# PWM.net
KiCad netlist of a schematic drawn in EAGLE
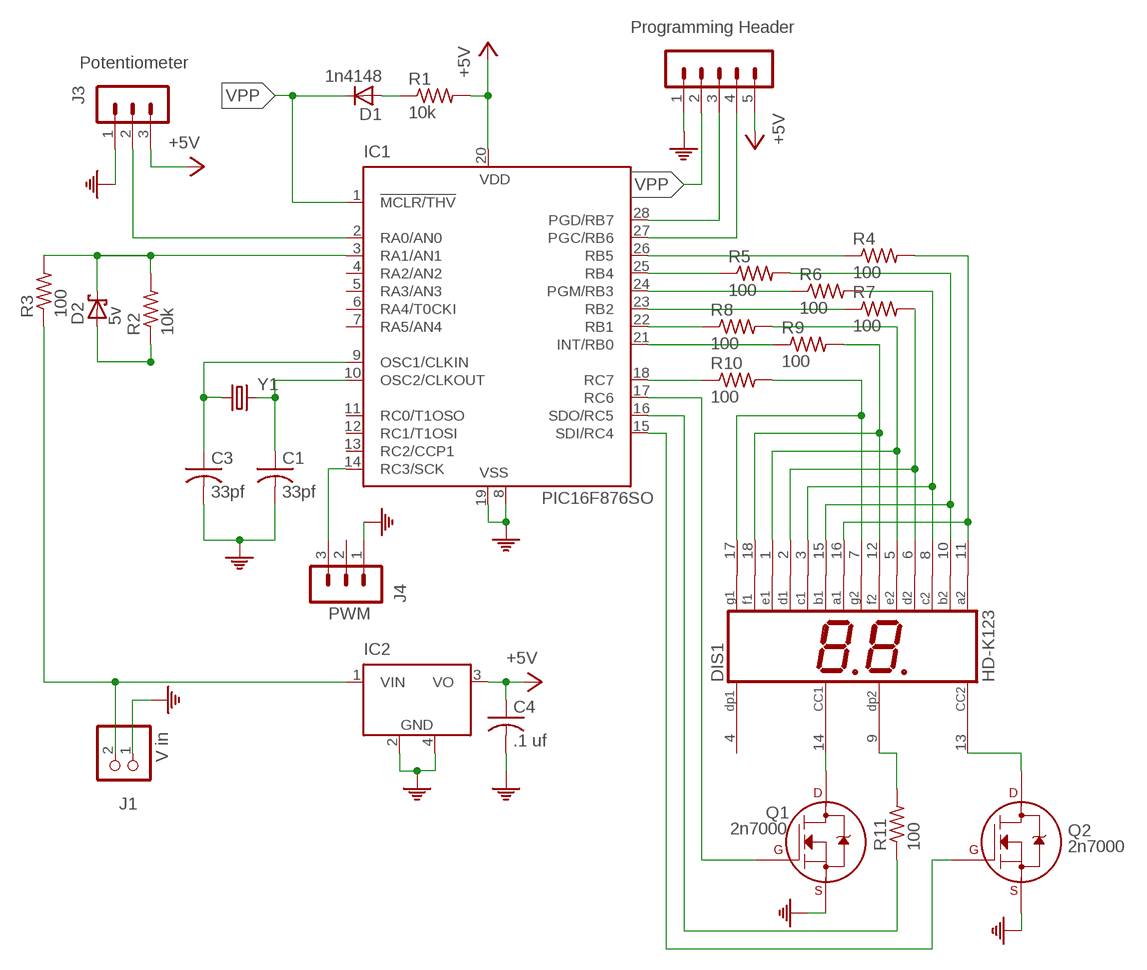
[diagram p0: schematic, sheet 1]

(export (version "E")
  (design (tool "Eeschema 10.0.6"))
  (components
    (comp (ref "C1")
      (value "33pf")
      (footprint "eagle-import:C0402K")
      (libsource (lib "eagle-import") (part "C-USC0402K"))
    )
    (comp (ref "C3")
      (value "33pf")
      (footprint "eagle-import:C0402K")
      (libsource (lib "eagle-import") (part "C-USC0402K"))
    )
    (comp (ref "C4")
      (value ".1 uf")
      (footprint "eagle-import:C0402K")
      (libsource (lib "eagle-import") (part "C-USC0402K"))
    )
    (comp (ref "D1")
      (value "1n4148")
      (footprint "eagle-import:SOD123")
      (libsource (lib "eagle-import") (part "D-SOD123"))
    )
    (comp (ref "D2")
      (value "5v")
      (footprint "eagle-import:SOD323_ST")
      (libsource (lib "eagle-import") (part "BAT60J"))
    )
    (comp (ref "DIS1")
      (value "HD-K123")
      (footprint "eagle-import:HDSP-R")
      (libsource (lib "eagle-import") (part "HD-K123"))
    )
    (comp (ref "IC1")
      (value "PIC16F876SO")
      (footprint "eagle-import:SO28W")
      (fields (field (name "MF") "MICROCHIP") (field (name "MPN") "PIC16F876-20/SO"))
      (libsource (lib "eagle-import") (part "PIC16876SOF"))
    )
    (comp (ref "IC2")
      (value "LM2936MP-5.0")
      (footprint "eagle-import:SOT223")
      (fields (field (name "MF") "NATIONAL SEMICONDUCTOR") (field (name "MPN") "LM2936MP-5.0/NOPB"))
      (libsource (lib "eagle-import") (part "LM2936MP?-5.0"))
    )
    (comp (ref "J1")
      (value "V in")
      (footprint "eagle-import:1X02")
      (libsource (lib "eagle-import") (part "PINHD-1X2"))
    )
    (comp (ref "J2")
      (value "Programming Header")
      (footprint "eagle-import:MA05-1")
      (libsource (lib "eagle-import") (part "MA05-1"))
    )
    (comp (ref "J3")
      (value "Potentiometer")
      (footprint "eagle-import:MA03-1")
      (libsource (lib "eagle-import") (part "MA03-1"))
    )
    (comp (ref "J4")
      (value "PWM")
      (footprint "eagle-import:MA03-1")
      (libsource (lib "eagle-import") (part "MA03-1"))
    )
    (comp (ref "Q1")
      (value "2n7000")
      (footprint "eagle-import:TO-92")
      (libsource (lib "eagle-import") (part "2N700_TO920"))
    )
    (comp (ref "Q2")
      (value "2n7000")
      (footprint "eagle-import:TO-92")
      (libsource (lib "eagle-import") (part "2N700_TO920"))
    )
    (comp (ref "R1")
      (value "10k")
      (footprint "eagle-import:R2012")
      (libsource (lib "eagle-import") (part "R-US_R2012"))
    )
    (comp (ref "R2")
      (value "10k")
      (footprint "eagle-import:R2012")
      (libsource (lib "eagle-import") (part "R-US_R2012"))
    )
    (comp (ref "R3")
      (value "100")
      (footprint "eagle-import:R2012")
      (libsource (lib "eagle-import") (part "R-US_R2012"))
    )
    (comp (ref "R4")
      (value "100")
      (footprint "eagle-import:R2012")
      (libsource (lib "eagle-import") (part "R-US_R2012"))
    )
    (comp (ref "R5")
      (value "100")
      (footprint "eagle-import:R2012")
      (libsource (lib "eagle-import") (part "R-US_R2012"))
    )
    (comp (ref "R6")
      (value "100")
      (footprint "eagle-import:R2012")
      (libsource (lib "eagle-import") (part "R-US_R2012"))
    )
    (comp (ref "R7")
      (value "100")
      (footprint "eagle-import:R2012")
      (libsource (lib "eagle-import") (part "R-US_R2012"))
    )
    (comp (ref "R8")
      (value "100")
      (footprint "eagle-import:R2012")
      (libsource (lib "eagle-import") (part "R-US_R2012"))
    )
    (comp (ref "R9")
      (value "100")
      (footprint "eagle-import:R2012")
      (libsource (lib "eagle-import") (part "R-US_R2012"))
    )
    (comp (ref "R10")
      (value "100")
      (footprint "eagle-import:R2012")
      (libsource (lib "eagle-import") (part "R-US_R2012"))
    )
    (comp (ref "R11")
      (value "100")
      (footprint "eagle-import:R2012")
      (libsource (lib "eagle-import") (part "R-US_R2012"))
    )
    (comp (ref "Y1")
      (value "CRYSTALHC49S")
      (footprint "eagle-import:HC49_S")
      (libsource (lib "eagle-import") (part "CRYSTALHC49S"))
    )
  )
  (nets
    (net (code "1") (name "+5V") (class "Default")
      (node (ref "C4") (pin "1") (pinfunction "1_1") (pintype "passive"))
      (node (ref "IC1") (pin "20") (pinfunction "VDD_20") (pintype "power_in"))
      (node (ref "IC2") (pin "3") (pinfunction "VO_3") (pintype "passive"))
      (node (ref "J2") (pin "5") (pinfunction "5_5") (pintype "passive"))
      (node (ref "J3") (pin "3") (pinfunction "3_3") (pintype "passive"))
      (node (ref "R1") (pin "2") (pinfunction "2_2") (pintype "passive"))
    )
    (net (code "2") (name "Net-(D1-A)") (class "Default")
      (node (ref "D1") (pin "2") (pinfunction "A_2") (pintype "passive"))
      (node (ref "R1") (pin "1") (pinfunction "1_1") (pintype "passive"))
    )
    (net (code "3") (name "Net-(D2-PadA)") (class "Default")
      (node (ref "D2") (pin "A") (pinfunction "A_A") (pintype "passive"))
      (node (ref "R2") (pin "1") (pinfunction "1_1") (pintype "passive"))
    )
    (net (code "4") (name "Net-(DIS1-A1)") (class "Default")
      (node (ref "DIS1") (pin "11") (pinfunction "A2_11") (pintype "passive"))
      (node (ref "DIS1") (pin "16") (pinfunction "A1_16") (pintype "passive"))
      (node (ref "R4") (pin "2") (pinfunction "2_2") (pintype "passive"))
    )
    (net (code "5") (name "Net-(DIS1-B1)") (class "Default")
      (node (ref "DIS1") (pin "10") (pinfunction "B2_10") (pintype "passive"))
      (node (ref "DIS1") (pin "15") (pinfunction "B1_15") (pintype "passive"))
      (node (ref "R5") (pin "2") (pinfunction "2_2") (pintype "passive"))
    )
    (net (code "6") (name "Net-(DIS1-C1)") (class "Default")
      (node (ref "DIS1") (pin "3") (pinfunction "C1_3") (pintype "passive"))
      (node (ref "DIS1") (pin "8") (pinfunction "C2_8") (pintype "passive"))
      (node (ref "R6") (pin "2") (pinfunction "2_2") (pintype "passive"))
    )
    (net (code "7") (name "Net-(DIS1-CC1)") (class "Default")
      (node (ref "DIS1") (pin "14") (pinfunction "CC1_14") (pintype "passive"))
      (node (ref "Q1") (pin "3") (pinfunction "D_3") (pintype "bidirectional"))
    )
    (net (code "8") (name "Net-(DIS1-CC2)") (class "Default")
      (node (ref "DIS1") (pin "13") (pinfunction "CC2_13") (pintype "passive"))
      (node (ref "Q2") (pin "3") (pinfunction "D_3") (pintype "bidirectional"))
    )
    (net (code "9") (name "Net-(DIS1-D1)") (class "Default")
      (node (ref "DIS1") (pin "2") (pinfunction "D1_2") (pintype "passive"))
      (node (ref "DIS1") (pin "6") (pinfunction "D2_6") (pintype "passive"))
      (node (ref "R7") (pin "2") (pinfunction "2_2") (pintype "passive"))
    )
    (net (code "10") (name "Net-(DIS1-DP2)") (class "Default")
      (node (ref "DIS1") (pin "9") (pinfunction "DP2_9") (pintype "passive"))
      (node (ref "R11") (pin "2") (pinfunction "2_2") (pintype "passive"))
    )
    (net (code "11") (name "Net-(DIS1-E1)") (class "Default")
      (node (ref "DIS1") (pin "1") (pinfunction "E1_1") (pintype "passive"))
      (node (ref "DIS1") (pin "5") (pinfunction "E2_5") (pintype "passive"))
      (node (ref "R8") (pin "2") (pinfunction "2_2") (pintype "passive"))
    )
    (net (code "12") (name "Net-(DIS1-F1)") (class "Default")
      (node (ref "DIS1") (pin "12") (pinfunction "F2_12") (pintype "passive"))
      (node (ref "DIS1") (pin "18") (pinfunction "F1_18") (pintype "passive"))
      (node (ref "R9") (pin "2") (pinfunction "2_2") (pintype "passive"))
    )
    (net (code "13") (name "Net-(DIS1-G1)") (class "Default")
      (node (ref "DIS1") (pin "17") (pinfunction "G1_17") (pintype "passive"))
      (node (ref "DIS1") (pin "7") (pinfunction "G2_7") (pintype "passive"))
      (node (ref "R10") (pin "2") (pinfunction "2_2") (pintype "passive"))
    )
    (net (code "14") (name "Net-(IC1-INT{slash}RB0)") (class "Default")
      (node (ref "IC1") (pin "21") (pinfunction "INT/RB0_21") (pintype "bidirectional"))
      (node (ref "R9") (pin "1") (pinfunction "1_1") (pintype "passive"))
    )
    (net (code "15") (name "Net-(IC1-OSC1{slash}CLKIN)") (class "Default")
      (node (ref "C3") (pin "1") (pinfunction "1_1") (pintype "passive"))
      (node (ref "IC1") (pin "9") (pinfunction "OSC1/CLKIN_9") (pintype "input"))
      (node (ref "Y1") (pin "1") (pinfunction "1_1") (pintype "passive"))
    )
    (net (code "16") (name "Net-(IC1-OSC2{slash}CLKOUT)") (class "Default")
      (node (ref "C1") (pin "1") (pinfunction "1_1") (pintype "passive"))
      (node (ref "IC1") (pin "10") (pinfunction "OSC2/CLKOUT_10") (pintype "output"))
      (node (ref "Y1") (pin "2") (pinfunction "2_2") (pintype "passive"))
    )
    (net (code "17") (name "Net-(IC1-PGC{slash}RB6)") (class "Default")
      (node (ref "IC1") (pin "27") (pinfunction "PGC/RB6_27") (pintype "bidirectional"))
      (node (ref "J2") (pin "4") (pinfunction "4_4") (pintype "passive"))
    )
    (net (code "18") (name "Net-(IC1-PGD{slash}RB7)") (class "Default")
      (node (ref "IC1") (pin "28") (pinfunction "PGD/RB7_28") (pintype "bidirectional"))
      (node (ref "J2") (pin "3") (pinfunction "3_3") (pintype "passive"))
    )
    (net (code "19") (name "Net-(IC1-PGM{slash}RB3)") (class "Default")
      (node (ref "IC1") (pin "24") (pinfunction "PGM/RB3_24") (pintype "bidirectional"))
      (node (ref "R6") (pin "1") (pinfunction "1_1") (pintype "passive"))
    )
    (net (code "20") (name "Net-(IC1-RA0{slash}AN0)") (class "Default")
      (node (ref "IC1") (pin "2") (pinfunction "RA0/AN0_2") (pintype "bidirectional"))
      (node (ref "J3") (pin "2") (pinfunction "2_2") (pintype "passive"))
    )
    (net (code "21") (name "Net-(IC1-RA1{slash}AN1)") (class "Default")
      (node (ref "D2") (pin "C") (pinfunction "C_C") (pintype "passive"))
      (node (ref "IC1") (pin "3") (pinfunction "RA1/AN1_3") (pintype "bidirectional"))
      (node (ref "R2") (pin "2") (pinfunction "2_2") (pintype "passive"))
      (node (ref "R3") (pin "2") (pinfunction "2_2") (pintype "passive"))
    )
    (net (code "22") (name "Net-(IC1-RB1)") (class "Default")
      (node (ref "IC1") (pin "22") (pinfunction "RB1_22") (pintype "bidirectional"))
      (node (ref "R8") (pin "1") (pinfunction "1_1") (pintype "passive"))
    )
    (net (code "23") (name "Net-(IC1-RB2)") (class "Default")
      (node (ref "IC1") (pin "23") (pinfunction "RB2_23") (pintype "bidirectional"))
      (node (ref "R7") (pin "1") (pinfunction "1_1") (pintype "passive"))
    )
    (net (code "24") (name "Net-(IC1-RB4)") (class "Default")
      (node (ref "IC1") (pin "25") (pinfunction "RB4_25") (pintype "bidirectional"))
      (node (ref "R5") (pin "1") (pinfunction "1_1") (pintype "passive"))
    )
    (net (code "25") (name "Net-(IC1-RB5)") (class "Default")
      (node (ref "IC1") (pin "26") (pinfunction "RB5_26") (pintype "bidirectional"))
      (node (ref "R4") (pin "1") (pinfunction "1_1") (pintype "passive"))
    )
    (net (code "26") (name "Net-(IC1-RC3{slash}SCK)") (class "Default")
      (node (ref "IC1") (pin "14") (pinfunction "RC3/SCK_14") (pintype "bidirectional"))
      (node (ref "J4") (pin "3") (pinfunction "3_3") (pintype "passive"))
    )
    (net (code "27") (name "Net-(IC1-RC6)") (class "Default")
      (node (ref "IC1") (pin "17") (pinfunction "RC6_17") (pintype "bidirectional"))
      (node (ref "Q1") (pin "2") (pinfunction "G_2") (pintype "tri_state"))
    )
    (net (code "28") (name "Net-(IC1-RC7)") (class "Default")
      (node (ref "IC1") (pin "18") (pinfunction "RC7_18") (pintype "bidirectional"))
      (node (ref "R10") (pin "1") (pinfunction "1_1") (pintype "passive"))
    )
    (net (code "29") (name "Net-(IC1-SDI{slash}RC4)") (class "Default")
      (node (ref "IC1") (pin "15") (pinfunction "SDI/RC4_15") (pintype "bidirectional"))
      (node (ref "Q2") (pin "2") (pinfunction "G_2") (pintype "tri_state"))
    )
    (net (code "30") (name "Net-(IC1-SDO{slash}RC5)") (class "Default")
      (node (ref "IC1") (pin "16") (pinfunction "SDO/RC5_16") (pintype "bidirectional"))
      (node (ref "R11") (pin "1") (pinfunction "1_1") (pintype "passive"))
    )
    (net (code "31") (name "Net-(IC2-VIN)") (class "Default")
      (node (ref "IC2") (pin "1") (pinfunction "VIN_1") (pintype "input"))
      (node (ref "J1") (pin "2") (pinfunction "2_2") (pintype "passive"))
      (node (ref "R3") (pin "1") (pinfunction "1_1") (pintype "passive"))
    )
    (net (code "32") (name "PE") (class "Default")
      (node (ref "C1") (pin "2") (pinfunction "2_2") (pintype "passive"))
      (node (ref "C3") (pin "2") (pinfunction "2_2") (pintype "passive"))
      (node (ref "C4") (pin "2") (pinfunction "2_2") (pintype "passive"))
      (node (ref "IC1") (pin "19") (pinfunction "VSS_19") (pintype "power_in"))
      (node (ref "IC1") (pin "8") (pinfunction "VSS_8") (pintype "power_in"))
      (node (ref "IC2") (pin "2") (pinfunction "GND_2") (pintype "passive"))
      (node (ref "IC2") (pin "4") (pinfunction "GND_4") (pintype "passive"))
      (node (ref "J1") (pin "1") (pinfunction "1_1") (pintype "passive"))
      (node (ref "J2") (pin "1") (pinfunction "1_1") (pintype "passive"))
      (node (ref "J3") (pin "1") (pinfunction "1_1") (pintype "passive"))
      (node (ref "J4") (pin "1") (pinfunction "1_1") (pintype "passive"))
      (node (ref "Q1") (pin "1") (pinfunction "S_1") (pintype "bidirectional"))
      (node (ref "Q2") (pin "1") (pinfunction "S_1") (pintype "bidirectional"))
    )
    (net (code "33") (name "VPP") (class "Default")
      (node (ref "D1") (pin "1") (pinfunction "C_1") (pintype "passive"))
      (node (ref "IC1") (pin "1") (pinfunction "~{MCLR/THV}_1") (pintype "input"))
      (node (ref "J2") (pin "2") (pinfunction "2_2") (pintype "passive"))
    )
    (net (code "34") (name "unconnected-(DIS1-DP1-Pad4)") (class "Default")
      (node (ref "DIS1") (pin "4") (pinfunction "DP1_4") (pintype "passive"))
    )
    (net (code "35") (name "unconnected-(IC1-RA2{slash}AN2-Pad4)") (class "Default")
      (node (ref "IC1") (pin "4") (pinfunction "RA2/AN2_4") (pintype "bidirectional"))
    )
    (net (code "36") (name "unconnected-(IC1-RA3{slash}AN3-Pad5)") (class "Default")
      (node (ref "IC1") (pin "5") (pinfunction "RA3/AN3_5") (pintype "bidirectional"))
    )
    (net (code "37") (name "unconnected-(IC1-RA4{slash}T0CKI-Pad6)") (class "Default")
      (node (ref "IC1") (pin "6") (pinfunction "RA4/T0CKI_6") (pintype "bidirectional"))
    )
    (net (code "38") (name "unconnected-(IC1-RA5{slash}AN4-Pad7)") (class "Default")
      (node (ref "IC1") (pin "7") (pinfunction "RA5/AN4_7") (pintype "bidirectional"))
    )
    (net (code "39") (name "unconnected-(IC1-RC0{slash}T1OSO-Pad11)") (class "Default")
      (node (ref "IC1") (pin "11") (pinfunction "RC0/T1OSO_11") (pintype "bidirectional"))
    )
    (net (code "40") (name "unconnected-(IC1-RC1{slash}T1OSI-Pad12)") (class "Default")
      (node (ref "IC1") (pin "12") (pinfunction "RC1/T1OSI_12") (pintype "bidirectional"))
    )
    (net (code "41") (name "unconnected-(IC1-RC2{slash}CCP1-Pad13)") (class "Default")
      (node (ref "IC1") (pin "13") (pinfunction "RC2/CCP1_13") (pintype "bidirectional"))
    )
    (net (code "42") (name "unconnected-(J4-Pad2)") (class "Default")
      (node (ref "J4") (pin "2") (pinfunction "2_2") (pintype "passive"))
    )
  )
)
